# headers.net
KiCad netlist of a schematic drawn in Altium Designer
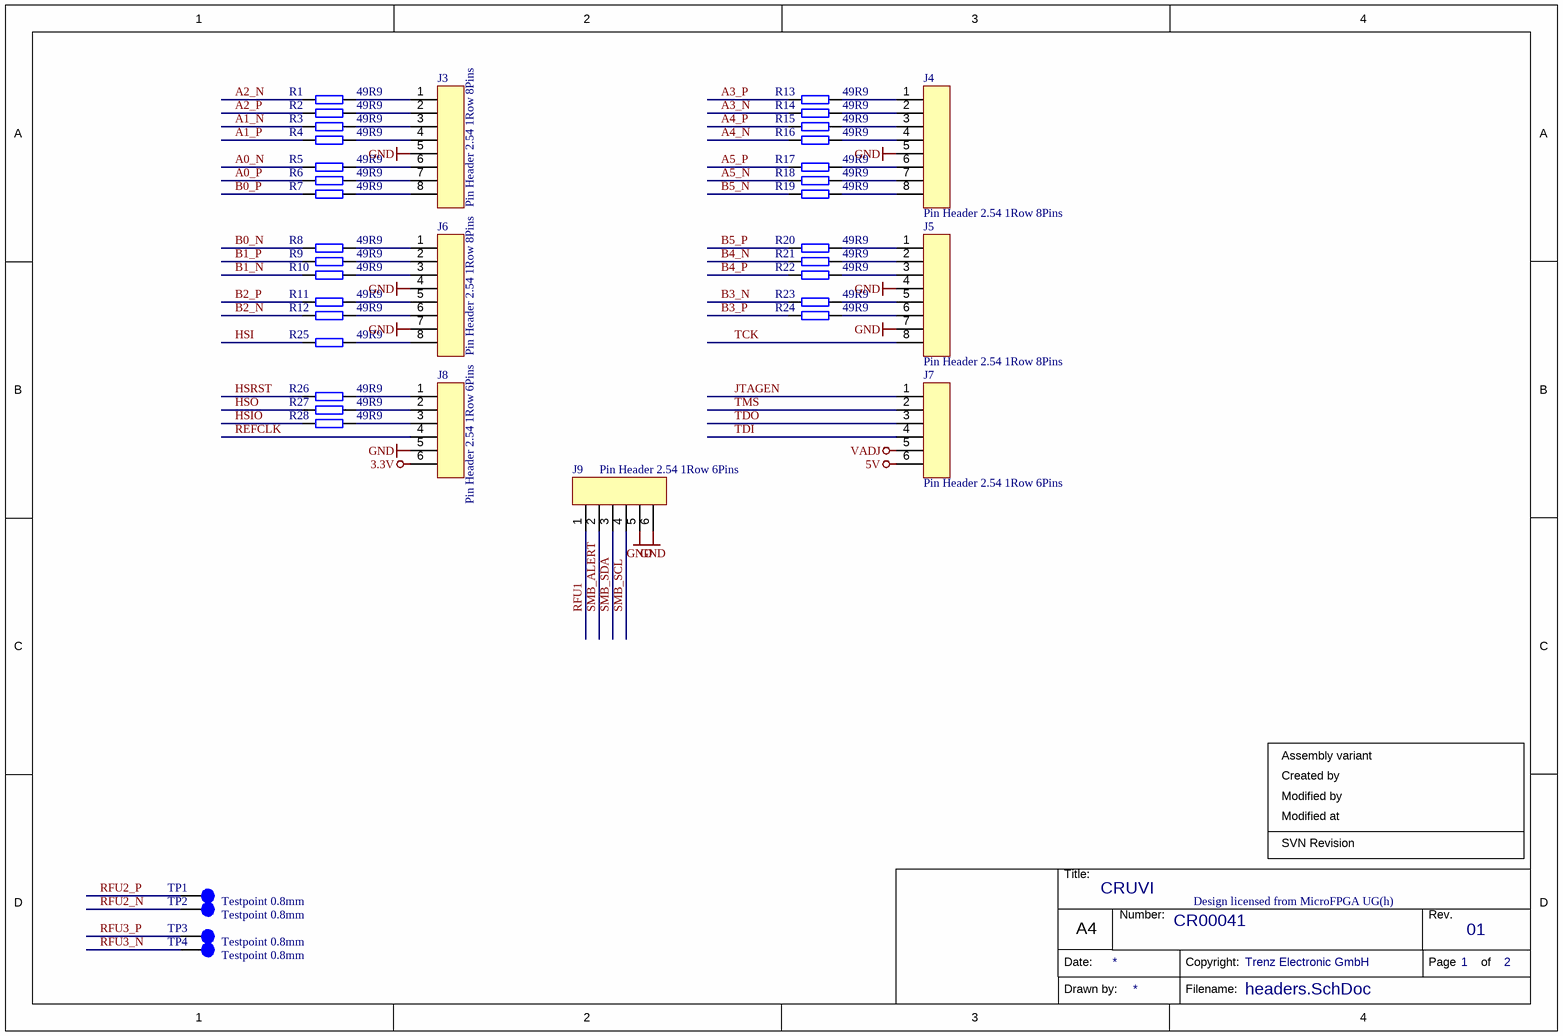
[diagram p0: headers.SchDoc]

(export (version "E")
  (design (tool "Eeschema 10.0.6"))
  (components
    (comp (ref "J3")
      (value "Pin Header 2.54 1Row 8Pins")
      (footprint "STIFTLEISTE2_54 OG 1R-8V")
      (description "Stiftleiste versetzt 1-reihig, 8pol.")
      (libsource (lib "TE") (part "CON-8"))
    )
    (comp (ref "J4")
      (value "Pin Header 2.54 1Row 8Pins")
      (footprint "STIFTLEISTE2_54 OG 1R-8V")
      (description "Stiftleiste versetzt 1-reihig, 8pol.")
      (libsource (lib "TE") (part "CON-8"))
    )
    (comp (ref "J5")
      (value "Pin Header 2.54 1Row 8Pins")
      (footprint "STIFTLEISTE2_54 OG 1R-8V")
      (description "Stiftleiste versetzt 1-reihig, 8pol.")
      (libsource (lib "TE") (part "CON-8"))
    )
    (comp (ref "J6")
      (value "Pin Header 2.54 1Row 8Pins")
      (footprint "STIFTLEISTE2_54 OG 1R-8V")
      (description "Stiftleiste versetzt 1-reihig, 8pol.")
      (libsource (lib "TE") (part "CON-8"))
    )
    (comp (ref "J7")
      (value "Pin Header 2.54 1Row 6Pins")
      (footprint "STIFTLEISTE2_54 OG 1R-6")
      (description "Stiftleiste gerade 1-reihig, 6pol")
      (libsource (lib "TE") (part "CON-6"))
    )
    (comp (ref "J8")
      (value "Pin Header 2.54 1Row 6Pins")
      (footprint "STIFTLEISTE2_54 OG 1R-6")
      (description "Stiftleiste gerade 1-reihig, 6pol")
      (libsource (lib "TE") (part "CON-6"))
    )
    (comp (ref "J9")
      (value "Pin Header 2.54 1Row 6Pins")
      (footprint "STIFTLEISTE2_54 OG 1R-6")
      (description "Stiftleiste gerade 1-reihig, 6pol")
      (libsource (lib "") (part "CON-6_1"))
    )
    (comp (ref "R1")
      (value "49R9")
      (footprint "RESC0603X26N_V")
      (description "WID SMD 49R9 1% 0,05W BF 0603 (0201)")
      (fields (field (name "TOLERANCE") "1%") (field (name "VOLTAGE") "25V"))
      (libsource (lib "TE") (part "RES"))
    )
    (comp (ref "R2")
      (value "49R9")
      (footprint "RESC0603X26N_V")
      (description "WID SMD 49R9 1% 0,05W BF 0603 (0201)")
      (fields (field (name "TOLERANCE") "1%") (field (name "VOLTAGE") "25V"))
      (libsource (lib "TE") (part "RES"))
    )
    (comp (ref "R3")
      (value "49R9")
      (footprint "RESC0603X26N_V")
      (description "WID SMD 49R9 1% 0,05W BF 0603 (0201)")
      (fields (field (name "TOLERANCE") "1%") (field (name "VOLTAGE") "25V"))
      (libsource (lib "TE") (part "RES"))
    )
    (comp (ref "R4")
      (value "49R9")
      (footprint "RESC0603X26N_V")
      (description "WID SMD 49R9 1% 0,05W BF 0603 (0201)")
      (fields (field (name "TOLERANCE") "1%") (field (name "VOLTAGE") "25V"))
      (libsource (lib "TE") (part "RES"))
    )
    (comp (ref "R5")
      (value "49R9")
      (footprint "RESC0603X26N_V")
      (description "WID SMD 49R9 1% 0,05W BF 0603 (0201)")
      (fields (field (name "TOLERANCE") "1%") (field (name "VOLTAGE") "25V"))
      (libsource (lib "TE") (part "RES"))
    )
    (comp (ref "R6")
      (value "49R9")
      (footprint "RESC0603X26N_V")
      (description "WID SMD 49R9 1% 0,05W BF 0603 (0201)")
      (fields (field (name "TOLERANCE") "1%") (field (name "VOLTAGE") "25V"))
      (libsource (lib "TE") (part "RES"))
    )
    (comp (ref "R7")
      (value "49R9")
      (footprint "RESC0603X26N_V")
      (description "WID SMD 49R9 1% 0,05W BF 0603 (0201)")
      (fields (field (name "TOLERANCE") "1%") (field (name "VOLTAGE") "25V"))
      (libsource (lib "TE") (part "RES"))
    )
    (comp (ref "R8")
      (value "49R9")
      (footprint "RESC0603X26N_V")
      (description "WID SMD 49R9 1% 0,05W BF 0603 (0201)")
      (fields (field (name "TOLERANCE") "1%") (field (name "VOLTAGE") "25V"))
      (libsource (lib "TE") (part "RES"))
    )
    (comp (ref "R9")
      (value "49R9")
      (footprint "RESC0603X26N_V")
      (description "WID SMD 49R9 1% 0,05W BF 0603 (0201)")
      (fields (field (name "TOLERANCE") "1%") (field (name "VOLTAGE") "25V"))
      (libsource (lib "TE") (part "RES"))
    )
    (comp (ref "R10")
      (value "49R9")
      (footprint "RESC0603X26N_V")
      (description "WID SMD 49R9 1% 0,05W BF 0603 (0201)")
      (fields (field (name "TOLERANCE") "1%") (field (name "VOLTAGE") "25V"))
      (libsource (lib "TE") (part "RES"))
    )
    (comp (ref "R11")
      (value "49R9")
      (footprint "RESC0603X26N_V")
      (description "WID SMD 49R9 1% 0,05W BF 0603 (0201)")
      (fields (field (name "TOLERANCE") "1%") (field (name "VOLTAGE") "25V"))
      (libsource (lib "TE") (part "RES"))
    )
    (comp (ref "R12")
      (value "49R9")
      (footprint "RESC0603X26N_V")
      (description "WID SMD 49R9 1% 0,05W BF 0603 (0201)")
      (fields (field (name "TOLERANCE") "1%") (field (name "VOLTAGE") "25V"))
      (libsource (lib "TE") (part "RES"))
    )
    (comp (ref "R13")
      (value "49R9")
      (footprint "RESC0603X26N_V")
      (description "WID SMD 49R9 1% 0,05W BF 0603 (0201)")
      (fields (field (name "TOLERANCE") "1%") (field (name "VOLTAGE") "25V"))
      (libsource (lib "TE") (part "RES"))
    )
    (comp (ref "R14")
      (value "49R9")
      (footprint "RESC0603X26N_V")
      (description "WID SMD 49R9 1% 0,05W BF 0603 (0201)")
      (fields (field (name "TOLERANCE") "1%") (field (name "VOLTAGE") "25V"))
      (libsource (lib "TE") (part "RES"))
    )
    (comp (ref "R15")
      (value "49R9")
      (footprint "RESC0603X26N_V")
      (description "WID SMD 49R9 1% 0,05W BF 0603 (0201)")
      (fields (field (name "TOLERANCE") "1%") (field (name "VOLTAGE") "25V"))
      (libsource (lib "TE") (part "RES"))
    )
    (comp (ref "R16")
      (value "49R9")
      (footprint "RESC0603X26N_V")
      (description "WID SMD 49R9 1% 0,05W BF 0603 (0201)")
      (fields (field (name "TOLERANCE") "1%") (field (name "VOLTAGE") "25V"))
      (libsource (lib "TE") (part "RES"))
    )
    (comp (ref "R17")
      (value "49R9")
      (footprint "RESC0603X26N_V")
      (description "WID SMD 49R9 1% 0,05W BF 0603 (0201)")
      (fields (field (name "TOLERANCE") "1%") (field (name "VOLTAGE") "25V"))
      (libsource (lib "TE") (part "RES"))
    )
    (comp (ref "R18")
      (value "49R9")
      (footprint "RESC0603X26N_V")
      (description "WID SMD 49R9 1% 0,05W BF 0603 (0201)")
      (fields (field (name "TOLERANCE") "1%") (field (name "VOLTAGE") "25V"))
      (libsource (lib "TE") (part "RES"))
    )
    (comp (ref "R19")
      (value "49R9")
      (footprint "RESC0603X26N_V")
      (description "WID SMD 49R9 1% 0,05W BF 0603 (0201)")
      (fields (field (name "TOLERANCE") "1%") (field (name "VOLTAGE") "25V"))
      (libsource (lib "TE") (part "RES"))
    )
    (comp (ref "R20")
      (value "49R9")
      (footprint "RESC0603X26N_V")
      (description "WID SMD 49R9 1% 0,05W BF 0603 (0201)")
      (fields (field (name "TOLERANCE") "1%") (field (name "VOLTAGE") "25V"))
      (libsource (lib "TE") (part "RES"))
    )
    (comp (ref "R21")
      (value "49R9")
      (footprint "RESC0603X26N_V")
      (description "WID SMD 49R9 1% 0,05W BF 0603 (0201)")
      (fields (field (name "TOLERANCE") "1%") (field (name "VOLTAGE") "25V"))
      (libsource (lib "TE") (part "RES"))
    )
    (comp (ref "R22")
      (value "49R9")
      (footprint "RESC0603X26N_V")
      (description "WID SMD 49R9 1% 0,05W BF 0603 (0201)")
      (fields (field (name "TOLERANCE") "1%") (field (name "VOLTAGE") "25V"))
      (libsource (lib "TE") (part "RES"))
    )
    (comp (ref "R23")
      (value "49R9")
      (footprint "RESC0603X26N_V")
      (description "WID SMD 49R9 1% 0,05W BF 0603 (0201)")
      (fields (field (name "TOLERANCE") "1%") (field (name "VOLTAGE") "25V"))
      (libsource (lib "TE") (part "RES"))
    )
    (comp (ref "R24")
      (value "49R9")
      (footprint "RESC0603X26N_V")
      (description "WID SMD 49R9 1% 0,05W BF 0603 (0201)")
      (fields (field (name "TOLERANCE") "1%") (field (name "VOLTAGE") "25V"))
      (libsource (lib "TE") (part "RES"))
    )
    (comp (ref "R25")
      (value "49R9")
      (footprint "RESC0603X26N_V")
      (description "WID SMD 49R9 1% 0,05W BF 0603 (0201)")
      (fields (field (name "TOLERANCE") "1%") (field (name "VOLTAGE") "25V"))
      (libsource (lib "TE") (part "RES"))
    )
    (comp (ref "R26")
      (value "49R9")
      (footprint "RESC0603X26N_V")
      (description "WID SMD 49R9 1% 0,05W BF 0603 (0201)")
      (fields (field (name "TOLERANCE") "1%") (field (name "VOLTAGE") "25V"))
      (libsource (lib "TE") (part "RES"))
    )
    (comp (ref "R27")
      (value "49R9")
      (footprint "RESC0603X26N_V")
      (description "WID SMD 49R9 1% 0,05W BF 0603 (0201)")
      (fields (field (name "TOLERANCE") "1%") (field (name "VOLTAGE") "25V"))
      (libsource (lib "TE") (part "RES"))
    )
    (comp (ref "R28")
      (value "49R9")
      (footprint "RESC0603X26N_V")
      (description "WID SMD 49R9 1% 0,05W BF 0603 (0201)")
      (fields (field (name "TOLERANCE") "1%") (field (name "VOLTAGE") "25V"))
      (libsource (lib "TE") (part "RES"))
    )
    (comp (ref "TP1") (value "Testpoint 0.8mm") (footprint "TP_0.8mm") (libsource (lib "TE") (part "TP")))
    (comp (ref "TP2") (value "Testpoint 0.8mm") (footprint "TP_0.8mm") (libsource (lib "TE") (part "TP")))
    (comp (ref "TP3") (value "Testpoint 0.8mm") (footprint "TP_0.8mm") (libsource (lib "TE") (part "TP")))
    (comp (ref "TP4") (value "Testpoint 0.8mm") (footprint "TP_0.8mm") (libsource (lib "TE") (part "TP")))
  )
  (nets
    (net (code "1") (name "/A0_N") (class "Default")
      (node (ref "R5") (pin "1") (pinfunction "1_1") (pintype "passive"))
    )
    (net (code "2") (name "/A0_P") (class "Default")
      (node (ref "R6") (pin "1") (pinfunction "1_1") (pintype "passive"))
    )
    (net (code "3") (name "/A1_N") (class "Default")
      (node (ref "R3") (pin "1") (pinfunction "1_1") (pintype "passive"))
    )
    (net (code "4") (name "/A1_P") (class "Default")
      (node (ref "R4") (pin "1") (pinfunction "1_1") (pintype "passive"))
    )
    (net (code "5") (name "/A2_N") (class "Default")
      (node (ref "R1") (pin "1") (pinfunction "1_1") (pintype "passive"))
    )
    (net (code "6") (name "/A2_P") (class "Default")
      (node (ref "R2") (pin "1") (pinfunction "1_1") (pintype "passive"))
    )
    (net (code "7") (name "/A3_N") (class "Default")
      (node (ref "R14") (pin "1") (pinfunction "1_1") (pintype "passive"))
    )
    (net (code "8") (name "/A3_P") (class "Default")
      (node (ref "R13") (pin "1") (pinfunction "1_1") (pintype "passive"))
    )
    (net (code "9") (name "/A4_N") (class "Default")
      (node (ref "R16") (pin "1") (pinfunction "1_1") (pintype "passive"))
    )
    (net (code "10") (name "/A4_P") (class "Default")
      (node (ref "R15") (pin "1") (pinfunction "1_1") (pintype "passive"))
    )
    (net (code "11") (name "/A5_N") (class "Default")
      (node (ref "R18") (pin "1") (pinfunction "1_1") (pintype "passive"))
    )
    (net (code "12") (name "/A5_P") (class "Default")
      (node (ref "R17") (pin "1") (pinfunction "1_1") (pintype "passive"))
    )
    (net (code "13") (name "/B0_N") (class "Default")
      (node (ref "R8") (pin "1") (pinfunction "1_1") (pintype "passive"))
    )
    (net (code "14") (name "/B0_P") (class "Default")
      (node (ref "R7") (pin "1") (pinfunction "1_1") (pintype "passive"))
    )
    (net (code "15") (name "/B1_N") (class "Default")
      (node (ref "R10") (pin "1") (pinfunction "1_1") (pintype "passive"))
    )
    (net (code "16") (name "/B1_P") (class "Default")
      (node (ref "R9") (pin "1") (pinfunction "1_1") (pintype "passive"))
    )
    (net (code "17") (name "/B2_N") (class "Default")
      (node (ref "R12") (pin "1") (pinfunction "1_1") (pintype "passive"))
    )
    (net (code "18") (name "/B2_P") (class "Default")
      (node (ref "R11") (pin "1") (pinfunction "1_1") (pintype "passive"))
    )
    (net (code "19") (name "/B3_N") (class "Default")
      (node (ref "R23") (pin "1") (pinfunction "1_1") (pintype "passive"))
    )
    (net (code "20") (name "/B3_P") (class "Default")
      (node (ref "R24") (pin "1") (pinfunction "1_1") (pintype "passive"))
    )
    (net (code "21") (name "/B4_N") (class "Default")
      (node (ref "R21") (pin "1") (pinfunction "1_1") (pintype "passive"))
    )
    (net (code "22") (name "/B4_P") (class "Default")
      (node (ref "R22") (pin "1") (pinfunction "1_1") (pintype "passive"))
    )
    (net (code "23") (name "/B5_N") (class "Default")
      (node (ref "R19") (pin "1") (pinfunction "1_1") (pintype "passive"))
    )
    (net (code "24") (name "/B5_P") (class "Default")
      (node (ref "R20") (pin "1") (pinfunction "1_1") (pintype "passive"))
    )
    (net (code "25") (name "/HSI") (class "Default")
      (node (ref "R25") (pin "1") (pinfunction "1_1") (pintype "passive"))
    )
    (net (code "26") (name "/HSIO") (class "Default")
      (node (ref "R28") (pin "1") (pinfunction "1_1") (pintype "passive"))
    )
    (net (code "27") (name "/HSO") (class "Default")
      (node (ref "R27") (pin "1") (pinfunction "1_1") (pintype "passive"))
    )
    (net (code "28") (name "/HSRST") (class "Default")
      (node (ref "R26") (pin "1") (pinfunction "1_1") (pintype "passive"))
    )
    (net (code "29") (name "/JTAGEN") (class "Default") (node (ref "J7") (pin "1") (pintype "passive")))
    (net (code "30") (name "/REFCLK") (class "Default") (node (ref "J8") (pin "4") (pintype "passive")))
    (net (code "31") (name "/RFU1") (class "Default") (node (ref "J9") (pin "1") (pintype "passive")))
    (net (code "32") (name "/RFU2_N") (class "Default") (node (ref "TP2") (pin "1") (pintype "passive")))
    (net (code "33") (name "/RFU2_P") (class "Default") (node (ref "TP1") (pin "1") (pintype "passive")))
    (net (code "34") (name "/RFU3_N") (class "Default") (node (ref "TP4") (pin "1") (pintype "passive")))
    (net (code "35") (name "/RFU3_P") (class "Default") (node (ref "TP3") (pin "1") (pintype "passive")))
    (net (code "36") (name "/SMB_ALERT") (class "Default") (node (ref "J9") (pin "2") (pintype "passive")))
    (net (code "37") (name "/SMB_SCL") (class "Default") (node (ref "J9") (pin "4") (pintype "passive")))
    (net (code "38") (name "/SMB_SDA") (class "Default") (node (ref "J9") (pin "3") (pintype "passive")))
    (net (code "39") (name "/TCK") (class "Default") (node (ref "J5") (pin "8") (pintype "passive")))
    (net (code "40") (name "/TDI") (class "Default") (node (ref "J7") (pin "4") (pintype "passive")))
    (net (code "41") (name "/TDO") (class "Default") (node (ref "J7") (pin "3") (pintype "passive")))
    (net (code "42") (name "/TMS") (class "Default") (node (ref "J7") (pin "2") (pintype "passive")))
    (net (code "43") (name "3.3V") (class "Default") (node (ref "J8") (pin "6") (pintype "passive")))
    (net (code "44") (name "5V") (class "Default") (node (ref "J7") (pin "6") (pintype "passive")))
    (net (code "45") (name "GND") (class "Default")
      (node (ref "J3") (pin "5") (pintype "passive"))
      (node (ref "J4") (pin "5") (pintype "passive"))
      (node (ref "J5") (pin "4") (pintype "passive"))
      (node (ref "J5") (pin "7") (pintype "passive"))
      (node (ref "J6") (pin "4") (pintype "passive"))
      (node (ref "J6") (pin "7") (pintype "passive"))
      (node (ref "J8") (pin "5") (pintype "passive"))
      (node (ref "J9") (pin "5") (pintype "passive"))
      (node (ref "J9") (pin "6") (pintype "passive"))
    )
    (net (code "46") (name "Net-(J3-Pad1)") (class "Default")
      (node (ref "J3") (pin "1") (pintype "passive"))
      (node (ref "R1") (pin "2") (pinfunction "2_2") (pintype "passive"))
    )
    (net (code "47") (name "Net-(J3-Pad2)") (class "Default")
      (node (ref "J3") (pin "2") (pintype "passive"))
      (node (ref "R2") (pin "2") (pinfunction "2_2") (pintype "passive"))
    )
    (net (code "48") (name "Net-(J3-Pad3)") (class "Default")
      (node (ref "J3") (pin "3") (pintype "passive"))
      (node (ref "R3") (pin "2") (pinfunction "2_2") (pintype "passive"))
    )
    (net (code "49") (name "Net-(J3-Pad4)") (class "Default")
      (node (ref "J3") (pin "4") (pintype "passive"))
      (node (ref "R4") (pin "2") (pinfunction "2_2") (pintype "passive"))
    )
    (net (code "50") (name "Net-(J3-Pad6)") (class "Default")
      (node (ref "J3") (pin "6") (pintype "passive"))
      (node (ref "R5") (pin "2") (pinfunction "2_2") (pintype "passive"))
    )
    (net (code "51") (name "Net-(J3-Pad7)") (class "Default")
      (node (ref "J3") (pin "7") (pintype "passive"))
      (node (ref "R6") (pin "2") (pinfunction "2_2") (pintype "passive"))
    )
    (net (code "52") (name "Net-(J3-Pad8)") (class "Default")
      (node (ref "J3") (pin "8") (pintype "passive"))
      (node (ref "R7") (pin "2") (pinfunction "2_2") (pintype "passive"))
    )
    (net (code "53") (name "Net-(J4-Pad1)") (class "Default")
      (node (ref "J4") (pin "1") (pintype "passive"))
      (node (ref "R13") (pin "2") (pinfunction "2_2") (pintype "passive"))
    )
    (net (code "54") (name "Net-(J4-Pad2)") (class "Default")
      (node (ref "J4") (pin "2") (pintype "passive"))
      (node (ref "R14") (pin "2") (pinfunction "2_2") (pintype "passive"))
    )
    (net (code "55") (name "Net-(J4-Pad3)") (class "Default")
      (node (ref "J4") (pin "3") (pintype "passive"))
      (node (ref "R15") (pin "2") (pinfunction "2_2") (pintype "passive"))
    )
    (net (code "56") (name "Net-(J4-Pad4)") (class "Default")
      (node (ref "J4") (pin "4") (pintype "passive"))
      (node (ref "R16") (pin "2") (pinfunction "2_2") (pintype "passive"))
    )
    (net (code "57") (name "Net-(J4-Pad6)") (class "Default")
      (node (ref "J4") (pin "6") (pintype "passive"))
      (node (ref "R17") (pin "2") (pinfunction "2_2") (pintype "passive"))
    )
    (net (code "58") (name "Net-(J4-Pad7)") (class "Default")
      (node (ref "J4") (pin "7") (pintype "passive"))
      (node (ref "R18") (pin "2") (pinfunction "2_2") (pintype "passive"))
    )
    (net (code "59") (name "Net-(J4-Pad8)") (class "Default")
      (node (ref "J4") (pin "8") (pintype "passive"))
      (node (ref "R19") (pin "2") (pinfunction "2_2") (pintype "passive"))
    )
    (net (code "60") (name "Net-(J5-Pad1)") (class "Default")
      (node (ref "J5") (pin "1") (pintype "passive"))
      (node (ref "R20") (pin "2") (pinfunction "2_2") (pintype "passive"))
    )
    (net (code "61") (name "Net-(J5-Pad2)") (class "Default")
      (node (ref "J5") (pin "2") (pintype "passive"))
      (node (ref "R21") (pin "2") (pinfunction "2_2") (pintype "passive"))
    )
    (net (code "62") (name "Net-(J5-Pad3)") (class "Default")
      (node (ref "J5") (pin "3") (pintype "passive"))
      (node (ref "R22") (pin "2") (pinfunction "2_2") (pintype "passive"))
    )
    (net (code "63") (name "Net-(J5-Pad5)") (class "Default")
      (node (ref "J5") (pin "5") (pintype "passive"))
      (node (ref "R23") (pin "2") (pinfunction "2_2") (pintype "passive"))
    )
    (net (code "64") (name "Net-(J5-Pad6)") (class "Default")
      (node (ref "J5") (pin "6") (pintype "passive"))
      (node (ref "R24") (pin "2") (pinfunction "2_2") (pintype "passive"))
    )
    (net (code "65") (name "Net-(J6-Pad1)") (class "Default")
      (node (ref "J6") (pin "1") (pintype "passive"))
      (node (ref "R8") (pin "2") (pinfunction "2_2") (pintype "passive"))
    )
    (net (code "66") (name "Net-(J6-Pad2)") (class "Default")
      (node (ref "J6") (pin "2") (pintype "passive"))
      (node (ref "R9") (pin "2") (pinfunction "2_2") (pintype "passive"))
    )
    (net (code "67") (name "Net-(J6-Pad3)") (class "Default")
      (node (ref "J6") (pin "3") (pintype "passive"))
      (node (ref "R10") (pin "2") (pinfunction "2_2") (pintype "passive"))
    )
    (net (code "68") (name "Net-(J6-Pad5)") (class "Default")
      (node (ref "J6") (pin "5") (pintype "passive"))
      (node (ref "R11") (pin "2") (pinfunction "2_2") (pintype "passive"))
    )
    (net (code "69") (name "Net-(J6-Pad6)") (class "Default")
      (node (ref "J6") (pin "6") (pintype "passive"))
      (node (ref "R12") (pin "2") (pinfunction "2_2") (pintype "passive"))
    )
    (net (code "70") (name "Net-(J6-Pad8)") (class "Default")
      (node (ref "J6") (pin "8") (pintype "passive"))
      (node (ref "R25") (pin "2") (pinfunction "2_2") (pintype "passive"))
    )
    (net (code "71") (name "Net-(J8-Pad1)") (class "Default")
      (node (ref "J8") (pin "1") (pintype "passive"))
      (node (ref "R26") (pin "2") (pinfunction "2_2") (pintype "passive"))
    )
    (net (code "72") (name "Net-(J8-Pad2)") (class "Default")
      (node (ref "J8") (pin "2") (pintype "passive"))
      (node (ref "R27") (pin "2") (pinfunction "2_2") (pintype "passive"))
    )
    (net (code "73") (name "Net-(J8-Pad3)") (class "Default")
      (node (ref "J8") (pin "3") (pintype "passive"))
      (node (ref "R28") (pin "2") (pinfunction "2_2") (pintype "passive"))
    )
    (net (code "74") (name "VADJ") (class "Default") (node (ref "J7") (pin "5") (pintype "passive")))
  )
)
